# Roaster_Control_-_Rev_I.net
KiCad netlist of a schematic drawn in EAGLE
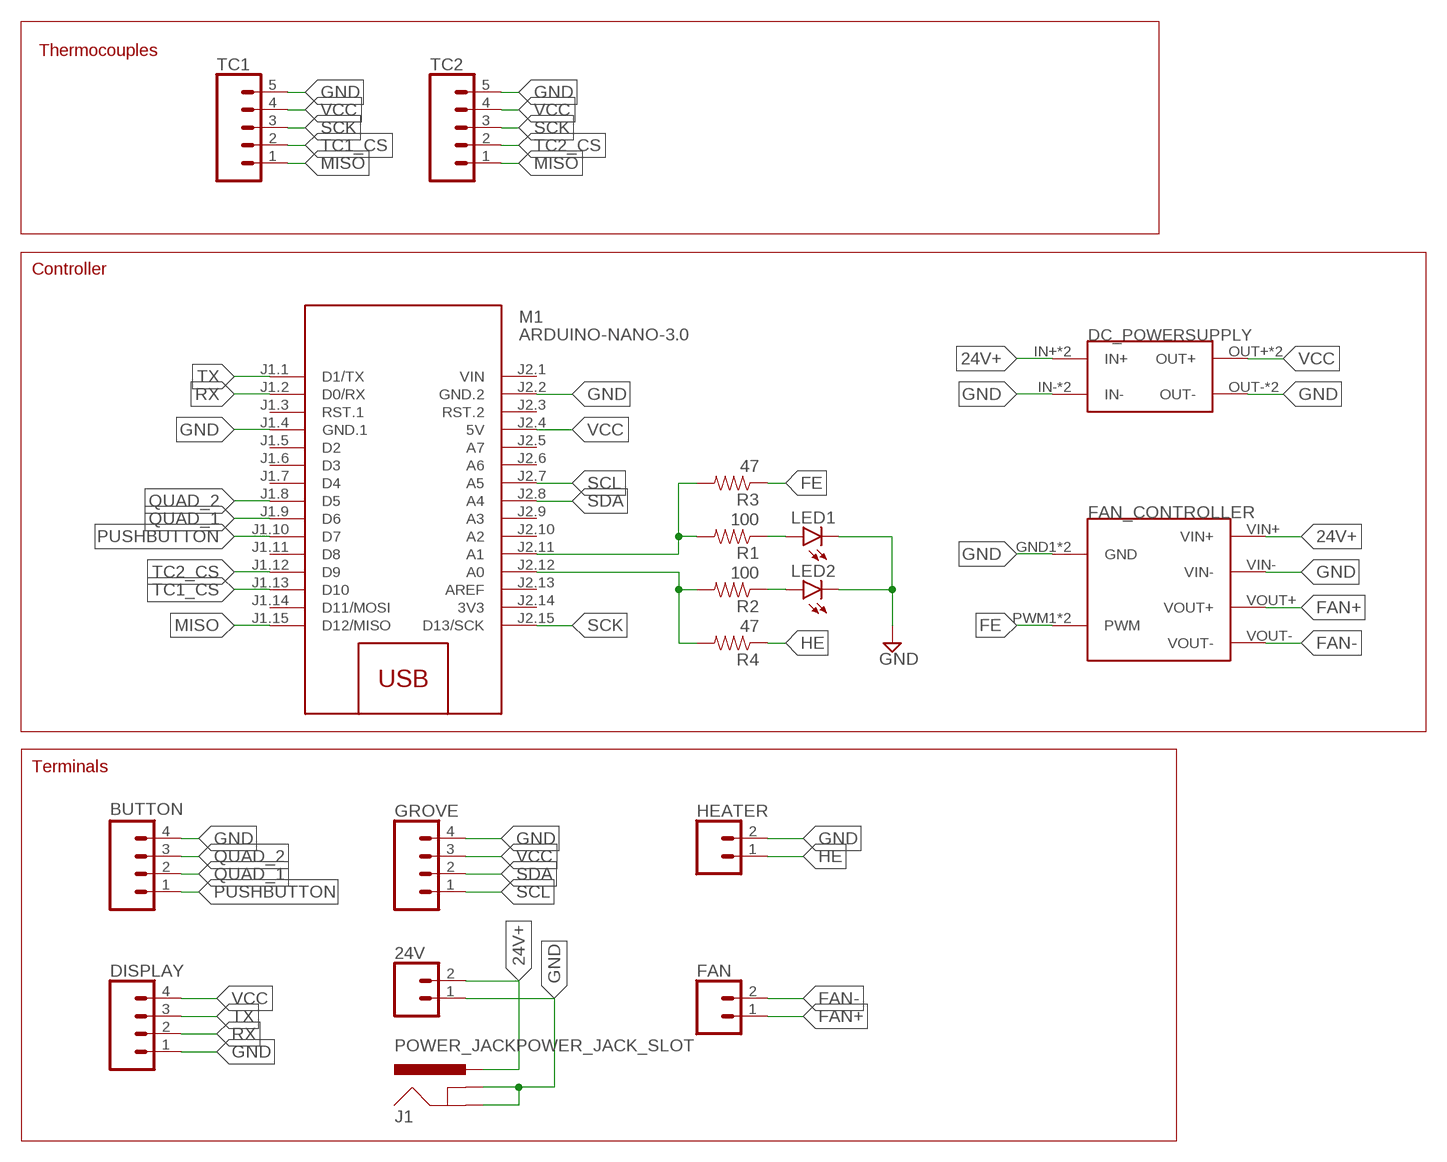
[diagram p0: schematic, sheet 1]

(export (version "E")
  (design (tool "Eeschema 10.0.6"))
  (components
    (comp (ref "24V")
      (value "CONN_02PTH3")
      (footprint "eagle-import:1X02_LONGPADS")
      (libsource (lib "eagle-import") (part "CONN_02PTH3"))
    )
    (comp (ref "BUTTON")
      (value "M04LONGPADS")
      (footprint "eagle-import:1X04_LONGPADS")
      (libsource (lib "eagle-import") (part "M04LONGPADS"))
    )
    (comp (ref "DC_POWERSUPPLY")
      (value "DCDC")
      (footprint "eagle-import:DCDC_FP")
      (libsource (lib "eagle-import") (part "DCDC"))
    )
    (comp (ref "DISPLAY")
      (value "CONN_04LONGPADS")
      (footprint "eagle-import:1X04_LONGPADS")
      (libsource (lib "eagle-import") (part "CONN_04LONGPADS"))
    )
    (comp (ref "FAN")
      (value "CONN_02PTH3")
      (footprint "eagle-import:1X02_LONGPADS")
      (libsource (lib "eagle-import") (part "CONN_02PTH3"))
    )
    (comp (ref "FAN_CONTROLLER")
      (value "DC_MC")
      (footprint "eagle-import:DC_MC_FP")
      (libsource (lib "eagle-import") (part "DC_MC"))
    )
    (comp (ref "GROVE")
      (value "CONN_04LONGPADS")
      (footprint "eagle-import:1X04_LONGPADS")
      (libsource (lib "eagle-import") (part "CONN_04LONGPADS"))
    )
    (comp (ref "HEATER")
      (value "CONN_02PTH3")
      (footprint "eagle-import:1X02_LONGPADS")
      (libsource (lib "eagle-import") (part "CONN_02PTH3"))
    )
    (comp (ref "J1")
      (value "POWER_JACKPOWER_JACK_SLOT")
      (footprint "eagle-import:POWER_JACK_PTH_SLOT")
      (libsource (lib "eagle-import") (part "POWER_JACKPOWER_JACK_SLOT"))
    )
    (comp (ref "LED1")
      (value "LEDCHIP-LED0805")
      (footprint "eagle-import:CHIP-LED0805")
      (libsource (lib "eagle-import") (part "LEDCHIP-LED0805"))
    )
    (comp (ref "LED2")
      (value "LEDCHIP-LED0805")
      (footprint "eagle-import:CHIP-LED0805")
      (libsource (lib "eagle-import") (part "LEDCHIP-LED0805"))
    )
    (comp (ref "M1")
      (value "ARDUINO-NANO-3.0")
      (footprint "eagle-import:ARDUINO-NANO-3.0")
      (libsource (lib "eagle-import") (part "ARDUINO-NANO-3.0"))
    )
    (comp (ref "R1")
      (value "100")
      (footprint "eagle-import:0603")
      (libsource (lib "eagle-import") (part "RESISTOR0603"))
    )
    (comp (ref "R2")
      (value "100")
      (footprint "eagle-import:0603")
      (libsource (lib "eagle-import") (part "RESISTOR0603"))
    )
    (comp (ref "R3")
      (value "47")
      (footprint "eagle-import:0603")
      (libsource (lib "eagle-import") (part "RESISTOR0603"))
    )
    (comp (ref "R4")
      (value "47")
      (footprint "eagle-import:0603")
      (libsource (lib "eagle-import") (part "RESISTOR0603"))
    )
    (comp (ref "TC1")
      (value "CONN_05PTH_LONGPADS")
      (footprint "eagle-import:1X05_LONGPADS")
      (libsource (lib "eagle-import") (part "CONN_05PTH_LONGPADS"))
    )
    (comp (ref "TC2")
      (value "CONN_05PTH_LONGPADS")
      (footprint "eagle-import:1X05_LONGPADS")
      (libsource (lib "eagle-import") (part "CONN_05PTH_LONGPADS"))
    )
  )
  (nets
    (net (code "1") (name "/3V3") (class "Default")
      (node (ref "M1") (pin "J2.14") (pinfunction "3V3_J2.14") (pintype "power_in"))
    )
    (net (code "2") (name "/VIN") (class "Default")
      (node (ref "M1") (pin "J2.1") (pinfunction "VIN_J2.1") (pintype "power_in"))
    )
    (net (code "3") (name "24V+") (class "Default")
      (node (ref "24V") (pin "2") (pinfunction "2_2") (pintype "passive"))
      (node (ref "DC_POWERSUPPLY") (pin "IN+") (pinfunction "IN+_IN+") (pintype "bidirectional"))
      (node (ref "DC_POWERSUPPLY") (pin "IN+2") (pinfunction "IN+_IN+2") (pintype "bidirectional"))
      (node (ref "FAN_CONTROLLER") (pin "VIN+") (pinfunction "VIN+_VIN+") (pintype "bidirectional"))
      (node (ref "J1") (pin "PWR") (pinfunction "PWR_PWR") (pintype "bidirectional"))
    )
    (net (code "4") (name "FAN+") (class "Default")
      (node (ref "FAN") (pin "1") (pinfunction "1_1") (pintype "passive"))
      (node (ref "FAN_CONTROLLER") (pin "VOUT+") (pinfunction "VOUT+_VOUT+") (pintype "bidirectional"))
    )
    (net (code "5") (name "FAN-") (class "Default")
      (node (ref "FAN") (pin "2") (pinfunction "2_2") (pintype "passive"))
      (node (ref "FAN_CONTROLLER") (pin "VOUT-") (pinfunction "VOUT-_VOUT-") (pintype "bidirectional"))
    )
    (net (code "6") (name "FE") (class "Default")
      (node (ref "FAN_CONTROLLER") (pin "PWM1") (pinfunction "PWM_PWM1") (pintype "bidirectional"))
      (node (ref "FAN_CONTROLLER") (pin "PWM2") (pinfunction "PWM_PWM2") (pintype "bidirectional"))
      (node (ref "R3") (pin "1") (pinfunction "1_1") (pintype "passive"))
    )
    (net (code "7") (name "GND") (class "Default")
      (node (ref "24V") (pin "1") (pinfunction "1_1") (pintype "passive"))
      (node (ref "BUTTON") (pin "4") (pinfunction "4_4") (pintype "passive"))
      (node (ref "DC_POWERSUPPLY") (pin "IN-") (pinfunction "IN-_IN-") (pintype "bidirectional"))
      (node (ref "DC_POWERSUPPLY") (pin "IN-2") (pinfunction "IN-_IN-2") (pintype "bidirectional"))
      (node (ref "DC_POWERSUPPLY") (pin "OUT-") (pinfunction "OUT-_OUT-") (pintype "bidirectional"))
      (node (ref "DC_POWERSUPPLY") (pin "OUT-2") (pinfunction "OUT-_OUT-2") (pintype "bidirectional"))
      (node (ref "DISPLAY") (pin "1") (pinfunction "1_1") (pintype "passive"))
      (node (ref "FAN_CONTROLLER") (pin "GND1") (pinfunction "GND_GND1") (pintype "bidirectional"))
      (node (ref "FAN_CONTROLLER") (pin "GND2") (pinfunction "GND_GND2") (pintype "bidirectional"))
      (node (ref "FAN_CONTROLLER") (pin "VIN-") (pinfunction "VIN-_VIN-") (pintype "bidirectional"))
      (node (ref "GROVE") (pin "4") (pinfunction "4_4") (pintype "passive"))
      (node (ref "HEATER") (pin "2") (pinfunction "2_2") (pintype "passive"))
      (node (ref "J1") (pin "GND") (pinfunction "GND_GND") (pintype "bidirectional"))
      (node (ref "J1") (pin "GNDBREAK") (pinfunction "GNDBREAK_GNDBREAK") (pintype "bidirectional"))
      (node (ref "LED1") (pin "C") (pinfunction "C_C") (pintype "passive"))
      (node (ref "LED2") (pin "C") (pinfunction "C_C") (pintype "passive"))
      (node (ref "M1") (pin "J1.4") (pinfunction "GND.1_J1.4") (pintype "power_in"))
      (node (ref "M1") (pin "J2.2") (pinfunction "GND.2_J2.2") (pintype "power_in"))
      (node (ref "TC1") (pin "5") (pinfunction "5_5") (pintype "passive"))
      (node (ref "TC2") (pin "5") (pinfunction "5_5") (pintype "passive"))
    )
    (net (code "8") (name "HE") (class "Default")
      (node (ref "HEATER") (pin "1") (pinfunction "1_1") (pintype "passive"))
      (node (ref "R4") (pin "1") (pinfunction "1_1") (pintype "passive"))
    )
    (net (code "9") (name "MISO") (class "Default")
      (node (ref "M1") (pin "J1.15") (pinfunction "D12/MISO_J1.15") (pintype "bidirectional"))
      (node (ref "TC1") (pin "1") (pinfunction "1_1") (pintype "passive"))
      (node (ref "TC2") (pin "1") (pinfunction "1_1") (pintype "passive"))
    )
    (net (code "10") (name "Net-(LED1-PadA)") (class "Default")
      (node (ref "LED1") (pin "A") (pinfunction "A_A") (pintype "passive"))
      (node (ref "R1") (pin "1") (pinfunction "1_1") (pintype "passive"))
    )
    (net (code "11") (name "Net-(LED2-PadA)") (class "Default")
      (node (ref "LED2") (pin "A") (pinfunction "A_A") (pintype "passive"))
      (node (ref "R2") (pin "1") (pinfunction "1_1") (pintype "passive"))
    )
    (net (code "12") (name "Net-(M1-A0)") (class "Default")
      (node (ref "M1") (pin "J2.12") (pinfunction "A0_J2.12") (pintype "bidirectional"))
      (node (ref "R2") (pin "2") (pinfunction "2_2") (pintype "passive"))
      (node (ref "R4") (pin "2") (pinfunction "2_2") (pintype "passive"))
    )
    (net (code "13") (name "Net-(M1-A1)") (class "Default")
      (node (ref "M1") (pin "J2.11") (pinfunction "A1_J2.11") (pintype "bidirectional"))
      (node (ref "R1") (pin "2") (pinfunction "2_2") (pintype "passive"))
      (node (ref "R3") (pin "2") (pinfunction "2_2") (pintype "passive"))
    )
    (net (code "14") (name "PUSHBUTTON") (class "Default")
      (node (ref "BUTTON") (pin "1") (pinfunction "1_1") (pintype "passive"))
      (node (ref "M1") (pin "J1.10") (pinfunction "D7_J1.10") (pintype "bidirectional"))
    )
    (net (code "15") (name "QUAD_1") (class "Default")
      (node (ref "BUTTON") (pin "2") (pinfunction "2_2") (pintype "passive"))
      (node (ref "M1") (pin "J1.9") (pinfunction "D6_J1.9") (pintype "bidirectional"))
    )
    (net (code "16") (name "QUAD_2") (class "Default")
      (node (ref "BUTTON") (pin "3") (pinfunction "3_3") (pintype "passive"))
      (node (ref "M1") (pin "J1.8") (pinfunction "D5_J1.8") (pintype "bidirectional"))
    )
    (net (code "17") (name "RX") (class "Default")
      (node (ref "DISPLAY") (pin "2") (pinfunction "2_2") (pintype "passive"))
      (node (ref "M1") (pin "J1.2") (pinfunction "D0/RX_J1.2") (pintype "bidirectional"))
    )
    (net (code "18") (name "SCK") (class "Default")
      (node (ref "M1") (pin "J2.15") (pinfunction "D13/SCK_J2.15") (pintype "bidirectional"))
      (node (ref "TC1") (pin "3") (pinfunction "3_3") (pintype "passive"))
      (node (ref "TC2") (pin "3") (pinfunction "3_3") (pintype "passive"))
    )
    (net (code "19") (name "SCL") (class "Default")
      (node (ref "GROVE") (pin "1") (pinfunction "1_1") (pintype "passive"))
      (node (ref "M1") (pin "J2.7") (pinfunction "A5_J2.7") (pintype "bidirectional"))
    )
    (net (code "20") (name "SDA") (class "Default")
      (node (ref "GROVE") (pin "2") (pinfunction "2_2") (pintype "passive"))
      (node (ref "M1") (pin "J2.8") (pinfunction "A4_J2.8") (pintype "bidirectional"))
    )
    (net (code "21") (name "TC1_CS") (class "Default")
      (node (ref "M1") (pin "J1.13") (pinfunction "D10_J1.13") (pintype "bidirectional"))
      (node (ref "TC1") (pin "2") (pinfunction "2_2") (pintype "passive"))
    )
    (net (code "22") (name "TC2_CS") (class "Default")
      (node (ref "M1") (pin "J1.12") (pinfunction "D9_J1.12") (pintype "bidirectional"))
      (node (ref "TC2") (pin "2") (pinfunction "2_2") (pintype "passive"))
    )
    (net (code "23") (name "TX") (class "Default")
      (node (ref "DISPLAY") (pin "3") (pinfunction "3_3") (pintype "passive"))
      (node (ref "M1") (pin "J1.1") (pinfunction "D1/TX_J1.1") (pintype "bidirectional"))
    )
    (net (code "24") (name "VCC") (class "Default")
      (node (ref "DC_POWERSUPPLY") (pin "OUT+") (pinfunction "OUT+_OUT+") (pintype "bidirectional"))
      (node (ref "DC_POWERSUPPLY") (pin "OUT+2") (pinfunction "OUT+_OUT+2") (pintype "bidirectional"))
      (node (ref "DISPLAY") (pin "4") (pinfunction "4_4") (pintype "passive"))
      (node (ref "GROVE") (pin "3") (pinfunction "3_3") (pintype "passive"))
      (node (ref "M1") (pin "J2.4") (pinfunction "5V_J2.4") (pintype "power_in"))
      (node (ref "TC1") (pin "4") (pinfunction "4_4") (pintype "passive"))
      (node (ref "TC2") (pin "4") (pinfunction "4_4") (pintype "passive"))
    )
    (net (code "25") (name "unconnected-(M1-A2-PadJ2.10)") (class "Default")
      (node (ref "M1") (pin "J2.10") (pinfunction "A2_J2.10") (pintype "bidirectional"))
    )
    (net (code "26") (name "unconnected-(M1-A3-PadJ2.9)") (class "Default")
      (node (ref "M1") (pin "J2.9") (pinfunction "A3_J2.9") (pintype "bidirectional"))
    )
    (net (code "27") (name "unconnected-(M1-A6-PadJ2.6)") (class "Default")
      (node (ref "M1") (pin "J2.6") (pinfunction "A6_J2.6") (pintype "bidirectional"))
    )
    (net (code "28") (name "unconnected-(M1-A7-PadJ2.5)") (class "Default")
      (node (ref "M1") (pin "J2.5") (pinfunction "A7_J2.5") (pintype "bidirectional"))
    )
    (net (code "29") (name "unconnected-(M1-AREF-PadJ2.13)") (class "Default")
      (node (ref "M1") (pin "J2.13") (pinfunction "AREF_J2.13") (pintype "bidirectional"))
    )
    (net (code "30") (name "unconnected-(M1-D2-PadJ1.5)") (class "Default")
      (node (ref "M1") (pin "J1.5") (pinfunction "D2_J1.5") (pintype "bidirectional"))
    )
    (net (code "31") (name "unconnected-(M1-D3-PadJ1.6)") (class "Default")
      (node (ref "M1") (pin "J1.6") (pinfunction "D3_J1.6") (pintype "bidirectional"))
    )
    (net (code "32") (name "unconnected-(M1-D4-PadJ1.7)") (class "Default")
      (node (ref "M1") (pin "J1.7") (pinfunction "D4_J1.7") (pintype "bidirectional"))
    )
    (net (code "33") (name "unconnected-(M1-D8-PadJ1.11)") (class "Default")
      (node (ref "M1") (pin "J1.11") (pinfunction "D8_J1.11") (pintype "bidirectional"))
    )
    (net (code "34") (name "unconnected-(M1-D11{slash}MOSI-PadJ1.14)") (class "Default")
      (node (ref "M1") (pin "J1.14") (pinfunction "D11/MOSI_J1.14") (pintype "bidirectional"))
    )
    (net (code "35") (name "unconnected-(M1-RST.1-PadJ1.3)") (class "Default")
      (node (ref "M1") (pin "J1.3") (pinfunction "RST.1_J1.3") (pintype "bidirectional"))
    )
    (net (code "36") (name "unconnected-(M1-RST.2-PadJ2.3)") (class "Default")
      (node (ref "M1") (pin "J2.3") (pinfunction "RST.2_J2.3") (pintype "bidirectional"))
    )
  )
)
